# LCD-Connecteur.net
KiCad netlist of a schematic drawn in Altium Designer
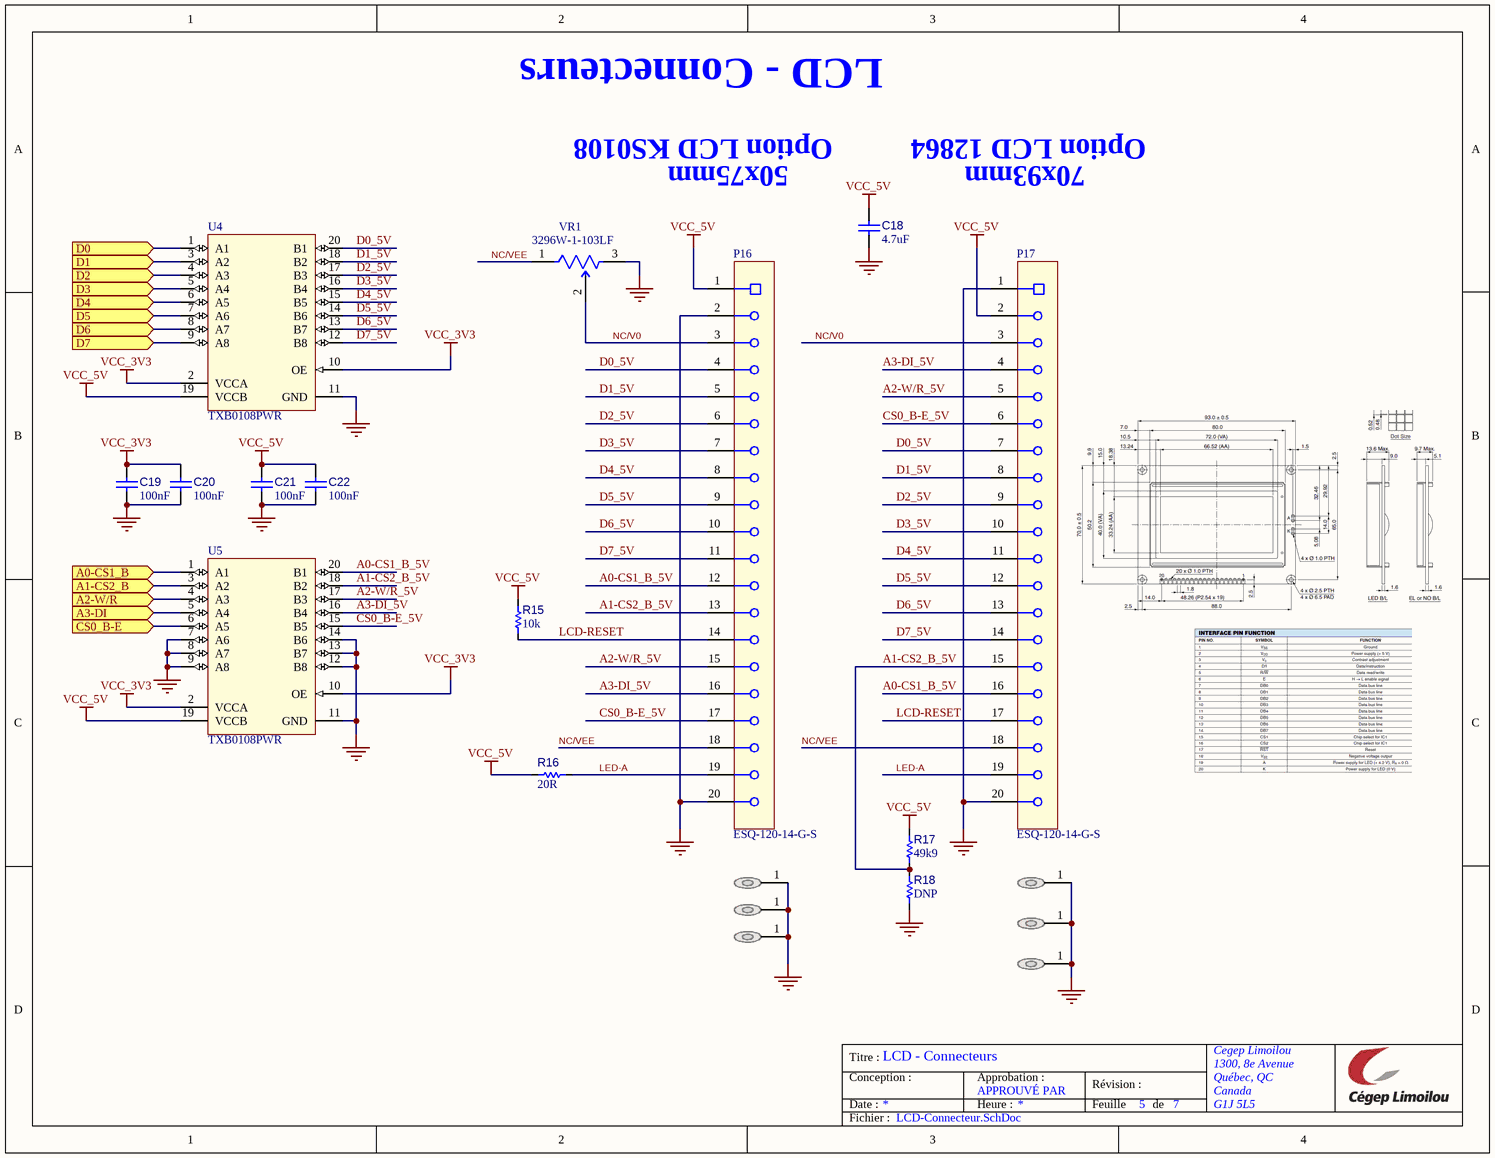
[diagram p0: LCD-Connecteur.SchDoc]

(export (version "E")
  (design (tool "Eeschema 10.0.6"))
  (components
    (comp (ref "C18")
      (value "4.7uF")
      (footprint "C_2012[0805]")
      (description "Capacitor type 1")
      (fields (field (name "TOLERANCE") "10%") (field (name "Comment") "Cap 4.7uF 0805"))
      (libsource (lib "TEP_243-Altium_DBLib") (part "capacitor"))
    )
    (comp (ref "C19")
      (value "100nF")
      (footprint "C_1005[0402]")
      (description "Capacitor type 1")
      (fields (field (name "TOLERANCE") "10%") (field (name "Comment") "Cap 100nF 0402"))
      (libsource (lib "TEP_243-Altium_DBLib") (part "capacitor"))
    )
    (comp (ref "C20")
      (value "100nF")
      (footprint "C_1005[0402]")
      (description "Capacitor type 1")
      (fields (field (name "TOLERANCE") "10%") (field (name "Comment") "Cap 100nF 0402"))
      (libsource (lib "TEP_243-Altium_DBLib") (part "capacitor"))
    )
    (comp (ref "C21")
      (value "100nF")
      (footprint "C_1005[0402]")
      (description "Capacitor type 1")
      (fields (field (name "TOLERANCE") "10%") (field (name "Comment") "Cap 100nF 0402"))
      (libsource (lib "TEP_243-Altium_DBLib") (part "capacitor"))
    )
    (comp (ref "C22")
      (value "100nF")
      (footprint "C_1005[0402]")
      (description "Capacitor type 1")
      (fields (field (name "TOLERANCE") "10%") (field (name "Comment") "Cap 100nF 0402"))
      (libsource (lib "TEP_243-Altium_DBLib") (part "capacitor"))
    )
    (comp (ref "MH6")
      (value "DNP")
      (footprint "MP_M-Hole_M2.5x0.45mm_LOOSE-FIT")
      (description "Mounting Hole 2.5mm w/ Flat Washer")
      (libsource (lib "TEP_243-AltiumLIB-Conn-TP-MH") (part "MH-2.5MM"))
    )
    (comp (ref "MH7")
      (value "DNP")
      (footprint "MP_M-Hole_M2.5x0.45mm_LOOSE-FIT")
      (description "Mounting Hole 2.5mm w/ Flat Washer")
      (libsource (lib "TEP_243-AltiumLIB-Conn-TP-MH") (part "MH-2.5MM"))
    )
    (comp (ref "MH8")
      (value "DNP")
      (footprint "MP_M-Hole_M2.5x0.45mm_LOOSE-FIT")
      (description "Mounting Hole 2.5mm w/ Flat Washer")
      (libsource (lib "TEP_243-AltiumLIB-Conn-TP-MH") (part "MH-2.5MM"))
    )
    (comp (ref "MH9")
      (value "DNP")
      (footprint "MP_M-Hole_M2.5x0.45mm_LOOSE-FIT")
      (description "Mounting Hole 2.5mm w/ Flat Washer")
      (libsource (lib "TEP_243-AltiumLIB-Conn-TP-MH") (part "MH-2.5MM"))
    )
    (comp (ref "MH10")
      (value "DNP")
      (footprint "MP_M-Hole_M2.5x0.45mm_LOOSE-FIT")
      (description "Mounting Hole 2.5mm w/ Flat Washer")
      (libsource (lib "TEP_243-AltiumLIB-Conn-TP-MH") (part "MH-2.5MM"))
    )
    (comp (ref "MH11")
      (value "DNP")
      (footprint "MP_M-Hole_M2.5x0.45mm_LOOSE-FIT")
      (description "Mounting Hole 2.5mm w/ Flat Washer")
      (libsource (lib "TEP_243-AltiumLIB-Conn-TP-MH") (part "MH-2.5MM"))
    )
    (comp (ref "P16")
      (value "ESQ-120-14-G-S")
      (footprint "CONN-SKT-20POS-100MIL")
      (description "CONN SOCKET 20POS 2.54MM")
      (libsource (lib "TEP_243-AltiumLIB-Conn-TP-MH") (part "CONN-100MIL-SKT-01X20"))
    )
    (comp (ref "P17")
      (value "ESQ-120-14-G-S")
      (footprint "CONN-SKT-20POS-100MIL")
      (description "CONN SOCKET 20POS 2.54MM")
      (libsource (lib "TEP_243-AltiumLIB-Conn-TP-MH") (part "CONN-100MIL-SKT-01X20"))
    )
    (comp (ref "R15")
      (value "10k")
      (footprint "R_1005[0402]")
      (description "Resistor type 1")
      (fields (field (name "TOLERANCE") "1%") (field (name "Comment") "Res 10k 1% 0402"))
      (libsource (lib "TEP_243-Altium_DBLib") (part "resistor"))
    )
    (comp (ref "R16")
      (value "20R")
      (footprint "R_3216[1206]")
      (description "Resistor type 1")
      (fields (field (name "TOLERANCE") "1%") (field (name "Comment") "Res 20R 1206"))
      (libsource (lib "TEP_243-Altium_DBLib") (part "resistor"))
    )
    (comp (ref "R17")
      (value "49k9")
      (footprint "R_1005[0402]")
      (description "Resistor type 1")
      (fields (field (name "TOLERANCE") "1%") (field (name "Comment") "Res 49k9 1% 0402"))
      (libsource (lib "TEP_243-Altium_DBLib") (part "resistor"))
    )
    (comp (ref "R18")
      (value "DNP")
      (footprint "R_1005[0402]")
      (description "Resistor type 1")
      (fields (field (name "TOLERANCE") "1%") (field (name "Comment") "Res 49k9 1% 0402"))
      (libsource (lib "TEP_243-Altium_DBLib") (part "resistor"))
    )
    (comp (ref "U4")
      (value "TXB0108PWR")
      (footprint "U_TSSOP65P660X450-20")
      (description "IC 8-Bit Bidirectional Voltage-Level Translator with Auto-Direction Sensing 20-Pin TSSOP (PW)")
      (libsource (lib "TEP_243-Altium_Library") (part "U_TXB0108PWR"))
    )
    (comp (ref "U5")
      (value "TXB0108PWR")
      (footprint "U_TSSOP65P660X450-20")
      (description "IC 8-Bit Bidirectional Voltage-Level Translator with Auto-Direction Sensing 20-Pin TSSOP (PW)")
      (libsource (lib "TEP_243-Altium_Library") (part "U_TXB0108PWR"))
    )
    (comp (ref "VR1")
      (value "3296W-1-103LF")
      (footprint "R-POT-TH-TOP")
      (description "TRIMMER 10K OHM 0.5W PC PIN TOP")
      (libsource (lib "TEP_243-Altium_Library") (part "RP-POT10K-MULTI-TURN-TOP-TH"))
    )
  )
  (nets
    (net (code "1") (name "/A0-CS1_B") (class "Default")
      (node (ref "U5") (pin "1") (pinfunction "A1_1") (pintype "bidirectional"))
    )
    (net (code "2") (name "/A0-CS1_B_5V") (class "Default")
      (node (ref "P16") (pin "12") (pinfunction "12_12") (pintype "passive"))
      (node (ref "P17") (pin "16") (pinfunction "16_16") (pintype "passive"))
      (node (ref "U5") (pin "20") (pinfunction "B1_20") (pintype "bidirectional"))
    )
    (net (code "3") (name "/A1-CS2_B") (class "Default")
      (node (ref "U5") (pin "3") (pinfunction "A2_3") (pintype "bidirectional"))
    )
    (net (code "4") (name "/A1-CS2_B_5V") (class "Default")
      (node (ref "P16") (pin "13") (pinfunction "13_13") (pintype "passive"))
      (node (ref "P17") (pin "15") (pinfunction "15_15") (pintype "passive"))
      (node (ref "R17") (pin "1") (pinfunction "1_1") (pintype "passive"))
      (node (ref "R18") (pin "2") (pinfunction "2_2") (pintype "passive"))
      (node (ref "U5") (pin "18") (pinfunction "B2_18") (pintype "bidirectional"))
    )
    (net (code "5") (name "/A2-W{slash}R") (class "Default")
      (node (ref "U5") (pin "4") (pinfunction "A3_4") (pintype "bidirectional"))
    )
    (net (code "6") (name "/A2-W{slash}R_5V") (class "Default")
      (node (ref "P16") (pin "15") (pinfunction "15_15") (pintype "passive"))
      (node (ref "P17") (pin "5") (pinfunction "5_5") (pintype "passive"))
      (node (ref "U5") (pin "17") (pinfunction "B3_17") (pintype "bidirectional"))
    )
    (net (code "7") (name "/A3-DI") (class "Default")
      (node (ref "U5") (pin "5") (pinfunction "A4_5") (pintype "bidirectional"))
    )
    (net (code "8") (name "/A3-DI_5V") (class "Default")
      (node (ref "P16") (pin "16") (pinfunction "16_16") (pintype "passive"))
      (node (ref "P17") (pin "4") (pinfunction "4_4") (pintype "passive"))
      (node (ref "U5") (pin "16") (pinfunction "B4_16") (pintype "bidirectional"))
    )
    (net (code "9") (name "/CS0_B-E") (class "Default")
      (node (ref "U5") (pin "6") (pinfunction "A5_6") (pintype "bidirectional"))
    )
    (net (code "10") (name "/CS0_B-E_5V") (class "Default")
      (node (ref "P16") (pin "17") (pinfunction "17_17") (pintype "passive"))
      (node (ref "P17") (pin "6") (pinfunction "6_6") (pintype "passive"))
      (node (ref "U5") (pin "15") (pinfunction "B5_15") (pintype "bidirectional"))
    )
    (net (code "11") (name "/D0") (class "Default")
      (node (ref "U4") (pin "1") (pinfunction "A1_1") (pintype "bidirectional"))
    )
    (net (code "12") (name "/D0_5V") (class "Default")
      (node (ref "P16") (pin "4") (pinfunction "4_4") (pintype "passive"))
      (node (ref "P17") (pin "7") (pinfunction "7_7") (pintype "passive"))
      (node (ref "U4") (pin "20") (pinfunction "B1_20") (pintype "bidirectional"))
    )
    (net (code "13") (name "/D1") (class "Default")
      (node (ref "U4") (pin "3") (pinfunction "A2_3") (pintype "bidirectional"))
    )
    (net (code "14") (name "/D1_5V") (class "Default")
      (node (ref "P16") (pin "5") (pinfunction "5_5") (pintype "passive"))
      (node (ref "P17") (pin "8") (pinfunction "8_8") (pintype "passive"))
      (node (ref "U4") (pin "18") (pinfunction "B2_18") (pintype "bidirectional"))
    )
    (net (code "15") (name "/D2") (class "Default")
      (node (ref "U4") (pin "4") (pinfunction "A3_4") (pintype "bidirectional"))
    )
    (net (code "16") (name "/D2_5V") (class "Default")
      (node (ref "P16") (pin "6") (pinfunction "6_6") (pintype "passive"))
      (node (ref "P17") (pin "9") (pinfunction "9_9") (pintype "passive"))
      (node (ref "U4") (pin "17") (pinfunction "B3_17") (pintype "bidirectional"))
    )
    (net (code "17") (name "/D3") (class "Default")
      (node (ref "U4") (pin "5") (pinfunction "A4_5") (pintype "bidirectional"))
    )
    (net (code "18") (name "/D3_5V") (class "Default")
      (node (ref "P16") (pin "7") (pinfunction "7_7") (pintype "passive"))
      (node (ref "P17") (pin "10") (pinfunction "10_10") (pintype "passive"))
      (node (ref "U4") (pin "16") (pinfunction "B4_16") (pintype "bidirectional"))
    )
    (net (code "19") (name "/D4") (class "Default")
      (node (ref "U4") (pin "6") (pinfunction "A5_6") (pintype "bidirectional"))
    )
    (net (code "20") (name "/D4_5V") (class "Default")
      (node (ref "P16") (pin "8") (pinfunction "8_8") (pintype "passive"))
      (node (ref "P17") (pin "11") (pinfunction "11_11") (pintype "passive"))
      (node (ref "U4") (pin "15") (pinfunction "B5_15") (pintype "bidirectional"))
    )
    (net (code "21") (name "/D5") (class "Default")
      (node (ref "U4") (pin "7") (pinfunction "A6_7") (pintype "bidirectional"))
    )
    (net (code "22") (name "/D5_5V") (class "Default")
      (node (ref "P16") (pin "9") (pinfunction "9_9") (pintype "passive"))
      (node (ref "P17") (pin "12") (pinfunction "12_12") (pintype "passive"))
      (node (ref "U4") (pin "14") (pinfunction "B6_14") (pintype "bidirectional"))
    )
    (net (code "23") (name "/D6") (class "Default")
      (node (ref "U4") (pin "8") (pinfunction "A7_8") (pintype "bidirectional"))
    )
    (net (code "24") (name "/D6_5V") (class "Default")
      (node (ref "P16") (pin "10") (pinfunction "10_10") (pintype "passive"))
      (node (ref "P17") (pin "13") (pinfunction "13_13") (pintype "passive"))
      (node (ref "U4") (pin "13") (pinfunction "B7_13") (pintype "bidirectional"))
    )
    (net (code "25") (name "/D7") (class "Default")
      (node (ref "U4") (pin "9") (pinfunction "A8_9") (pintype "bidirectional"))
    )
    (net (code "26") (name "/D7_5V") (class "Default")
      (node (ref "P16") (pin "11") (pinfunction "11_11") (pintype "passive"))
      (node (ref "P17") (pin "14") (pinfunction "14_14") (pintype "passive"))
      (node (ref "U4") (pin "12") (pinfunction "B8_12") (pintype "bidirectional"))
    )
    (net (code "27") (name "/LCD-RESET") (class "Default")
      (node (ref "P16") (pin "14") (pinfunction "14_14") (pintype "passive"))
      (node (ref "P17") (pin "17") (pinfunction "17_17") (pintype "passive"))
      (node (ref "R15") (pin "1") (pinfunction "1_1") (pintype "passive"))
    )
    (net (code "28") (name "/LED-A") (class "Default")
      (node (ref "P16") (pin "19") (pinfunction "19_19") (pintype "passive"))
      (node (ref "P17") (pin "19") (pinfunction "19_19") (pintype "passive"))
      (node (ref "R16") (pin "2") (pinfunction "2_2") (pintype "passive"))
    )
    (net (code "29") (name "/NC{slash}V0") (class "Default")
      (node (ref "P16") (pin "3") (pinfunction "3_3") (pintype "passive"))
      (node (ref "P17") (pin "3") (pinfunction "3_3") (pintype "passive"))
      (node (ref "VR1") (pin "2") (pinfunction "WIPER_2") (pintype "passive"))
    )
    (net (code "30") (name "/NC{slash}VEE") (class "Default")
      (node (ref "P16") (pin "18") (pinfunction "18_18") (pintype "passive"))
      (node (ref "P17") (pin "18") (pinfunction "18_18") (pintype "passive"))
      (node (ref "VR1") (pin "1") (pinfunction "CCW_1") (pintype "passive"))
    )
    (net (code "31") (name "GND") (class "Default")
      (node (ref "C18") (pin "1") (pinfunction "1_1") (pintype "passive"))
      (node (ref "C19") (pin "1") (pinfunction "1_1") (pintype "passive"))
      (node (ref "C20") (pin "1") (pinfunction "1_1") (pintype "passive"))
      (node (ref "C21") (pin "1") (pinfunction "1_1") (pintype "passive"))
      (node (ref "C22") (pin "1") (pinfunction "1_1") (pintype "passive"))
      (node (ref "MH10") (pin "1") (pinfunction "1_1") (pintype "power_in"))
      (node (ref "MH11") (pin "1") (pinfunction "1_1") (pintype "power_in"))
      (node (ref "MH6") (pin "1") (pinfunction "1_1") (pintype "power_in"))
      (node (ref "MH7") (pin "1") (pinfunction "1_1") (pintype "power_in"))
      (node (ref "MH8") (pin "1") (pinfunction "1_1") (pintype "power_in"))
      (node (ref "MH9") (pin "1") (pinfunction "1_1") (pintype "power_in"))
      (node (ref "P16") (pin "2") (pinfunction "2_2") (pintype "passive"))
      (node (ref "P16") (pin "20") (pinfunction "20_20") (pintype "passive"))
      (node (ref "P17") (pin "1") (pinfunction "1_1") (pintype "passive"))
      (node (ref "P17") (pin "20") (pinfunction "20_20") (pintype "passive"))
      (node (ref "R18") (pin "1") (pinfunction "1_1") (pintype "passive"))
      (node (ref "U4") (pin "11") (pinfunction "GND_11") (pintype "power_in"))
      (node (ref "U5") (pin "11") (pinfunction "GND_11") (pintype "power_in"))
      (node (ref "U5") (pin "12") (pinfunction "B8_12") (pintype "bidirectional"))
      (node (ref "U5") (pin "13") (pinfunction "B7_13") (pintype "bidirectional"))
      (node (ref "U5") (pin "14") (pinfunction "B6_14") (pintype "bidirectional"))
      (node (ref "U5") (pin "7") (pinfunction "A6_7") (pintype "bidirectional"))
      (node (ref "U5") (pin "8") (pinfunction "A7_8") (pintype "bidirectional"))
      (node (ref "U5") (pin "9") (pinfunction "A8_9") (pintype "bidirectional"))
      (node (ref "VR1") (pin "3") (pinfunction "CW_3") (pintype "passive"))
    )
    (net (code "32") (name "VCC_3V3") (class "Default")
      (node (ref "C19") (pin "2") (pinfunction "2_2") (pintype "passive"))
      (node (ref "C20") (pin "2") (pinfunction "2_2") (pintype "passive"))
      (node (ref "U4") (pin "10") (pinfunction "OE_10") (pintype "input"))
      (node (ref "U4") (pin "2") (pinfunction "VCCA_2") (pintype "power_in"))
      (node (ref "U5") (pin "10") (pinfunction "OE_10") (pintype "input"))
      (node (ref "U5") (pin "2") (pinfunction "VCCA_2") (pintype "power_in"))
    )
    (net (code "33") (name "VCC_5V") (class "Default")
      (node (ref "C18") (pin "2") (pinfunction "2_2") (pintype "passive"))
      (node (ref "C21") (pin "2") (pinfunction "2_2") (pintype "passive"))
      (node (ref "C22") (pin "2") (pinfunction "2_2") (pintype "passive"))
      (node (ref "P16") (pin "1") (pinfunction "1_1") (pintype "passive"))
      (node (ref "P17") (pin "2") (pinfunction "2_2") (pintype "passive"))
      (node (ref "R15") (pin "2") (pinfunction "2_2") (pintype "passive"))
      (node (ref "R16") (pin "1") (pinfunction "1_1") (pintype "passive"))
      (node (ref "R17") (pin "2") (pinfunction "2_2") (pintype "passive"))
      (node (ref "U4") (pin "19") (pinfunction "VCCB_19") (pintype "power_in"))
      (node (ref "U5") (pin "19") (pinfunction "VCCB_19") (pintype "power_in"))
    )
  )
)
